# Schematic.net
KiCad netlist of a schematic drawn in Altium Designer
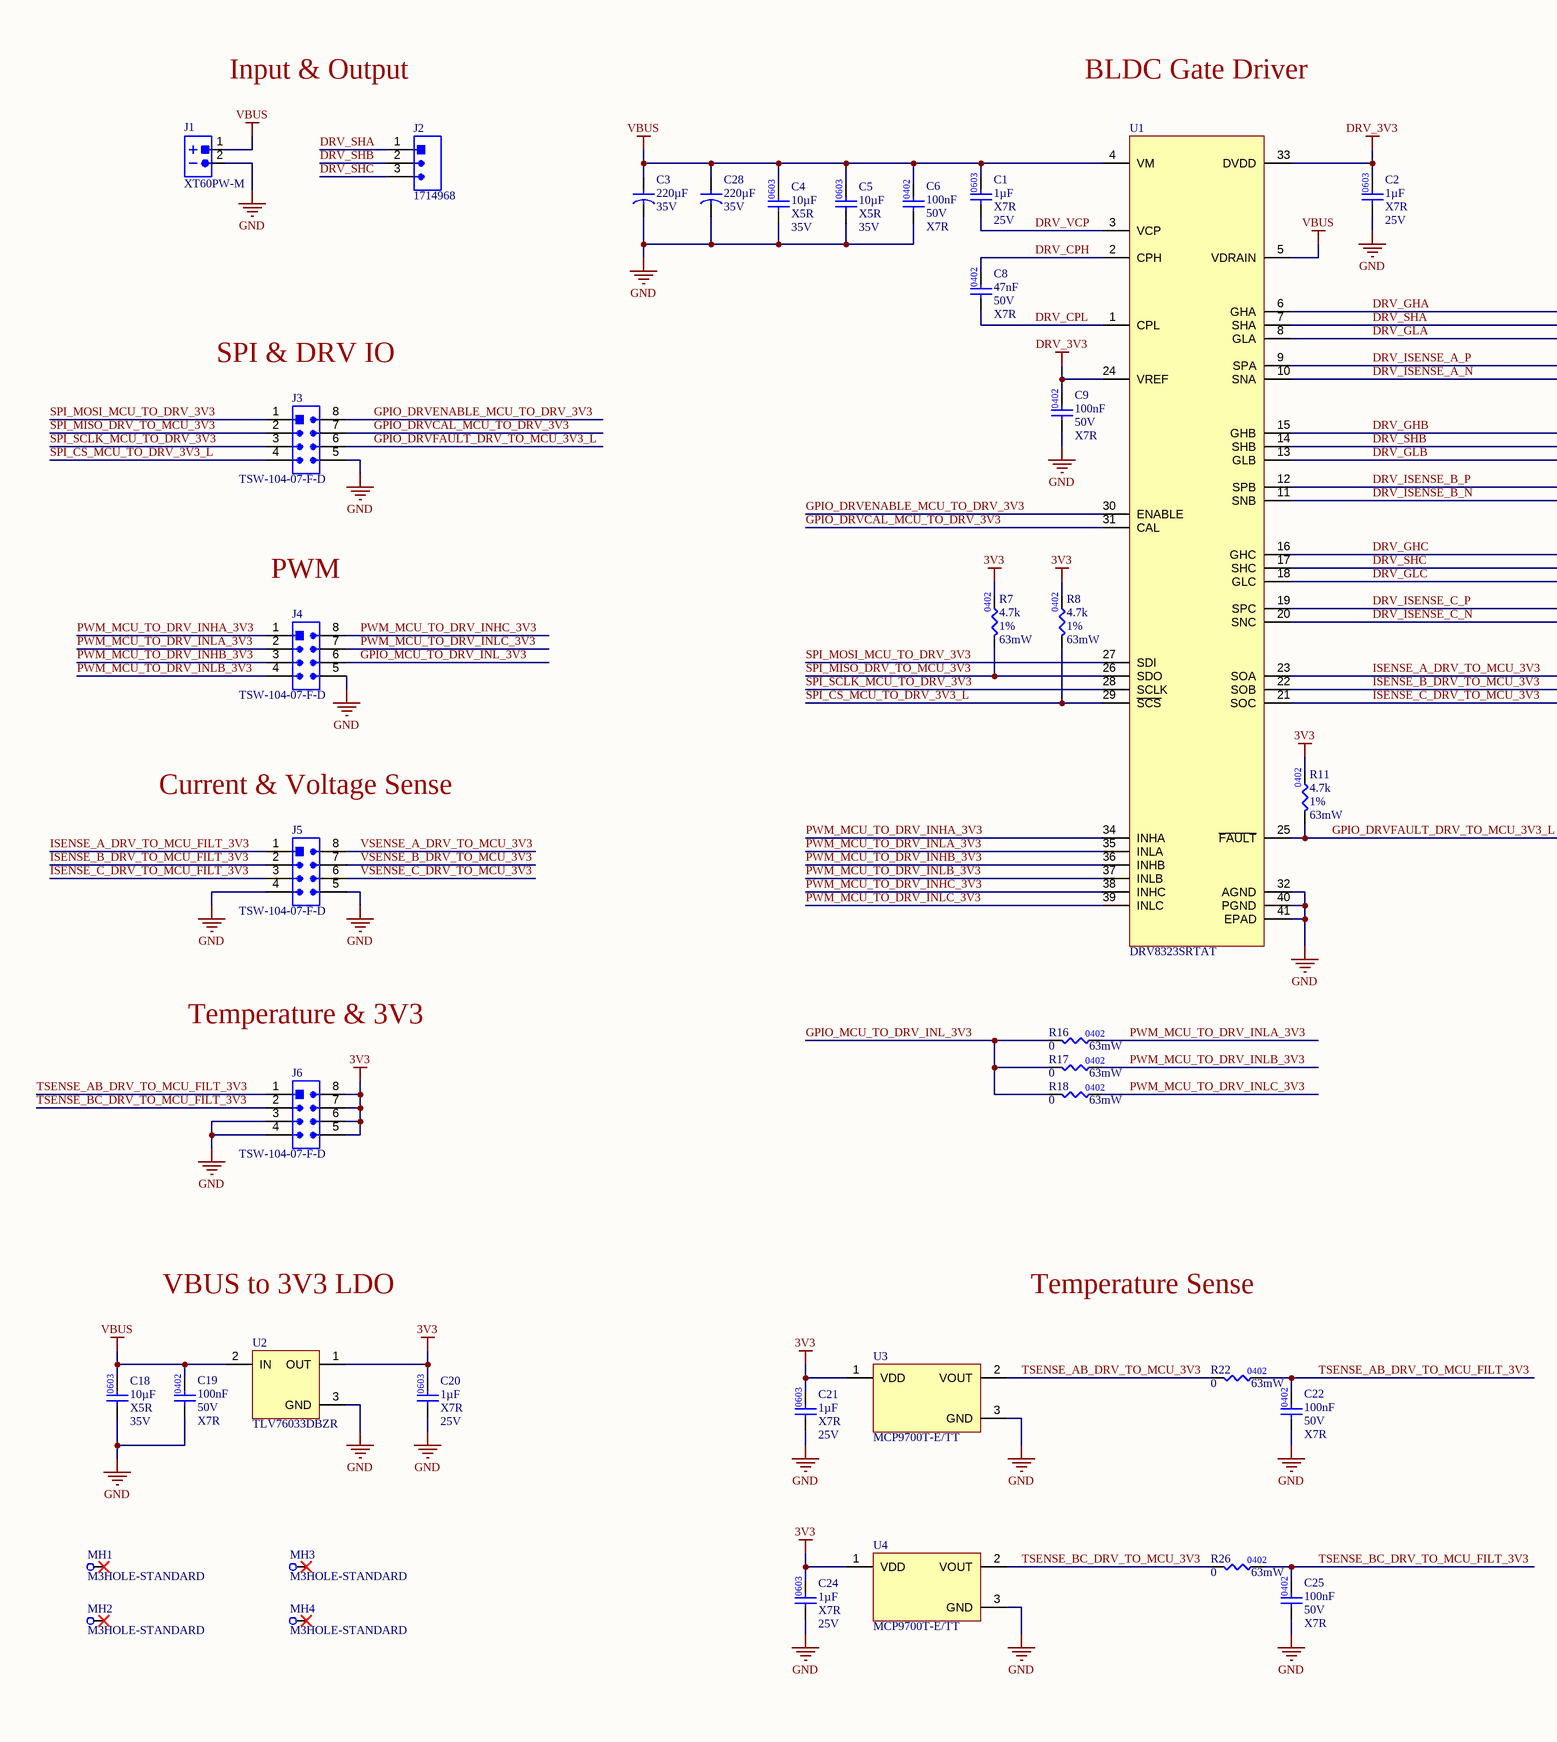
[diagram p0: Schematic.SchDoc, left]
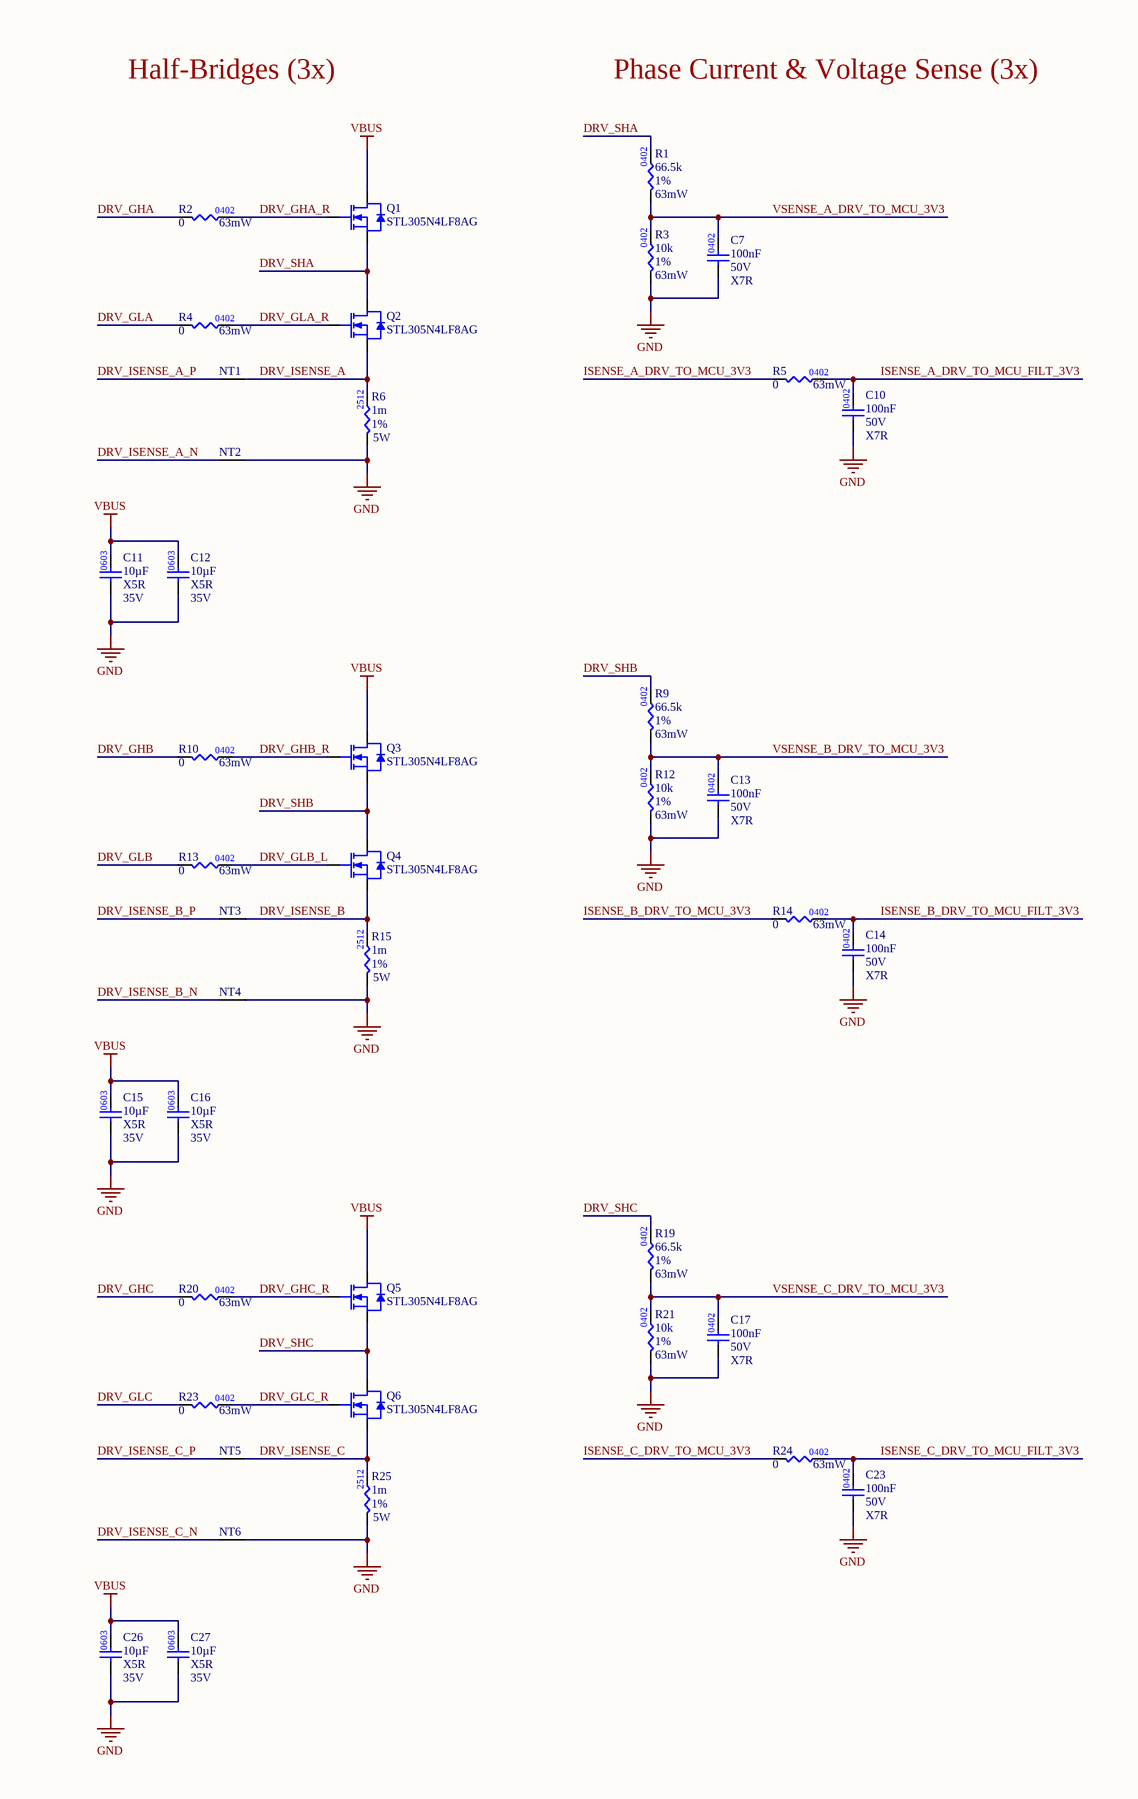
[diagram p1: Schematic.SchDoc, right]

(export (version "E")
  (design (tool "Eeschema 10.0.6"))
  (components
    (comp (ref "C1")
      (value "1µF")
      (footprint ".CAP_0603-Footprint-1")
      (description "CAP CER 1UF 25V X7R 0603")
      (fields
        (field (name "TEMPERATURE COEFFICIENT") "X7R")
        (field (name "VOLTAGE RATING") "25V")
        (field (name "TOLERANCE") "10%")
        (field (name "Comment") "CL10B105KA8NNNC")
      )
      (libsource (lib "Americas - University of Waterloo - Kevin Li Capstone 2025") (part ".CAP_0603-Symbol-1"))
    )
    (comp (ref "C2")
      (value "1µF")
      (footprint ".CAP_0603-Footprint-1")
      (description "CAP CER 1UF 25V X7R 0603")
      (fields
        (field (name "TEMPERATURE COEFFICIENT") "X7R")
        (field (name "VOLTAGE RATING") "25V")
        (field (name "TOLERANCE") "10%")
        (field (name "Comment") "CL10B105KA8NNNC")
      )
      (libsource (lib "Americas - University of Waterloo - Kevin Li Capstone 2025") (part ".CAP_0603-Symbol-1"))
    )
    (comp (ref "C3")
      (value "220µF")
      (footprint "865080553014-Footprint-1")
      (description "CAP ALUM 220UF 20% 35V SMD")
      (fields
        (field (name "TOLERANCE") "20%")
        (field (name "VOLTAGE RATING") "35V")
        (field (name "Comment") "865080553014")
      )
      (libsource (lib "Americas - University of Waterloo - Kevin Li Capstone 2025") (part "865080553014-Symbol-1"))
    )
    (comp (ref "C4")
      (value "10µF")
      (footprint ".CAP_0603-Footprint-1")
      (description "CAP CER 10UF 35V X5R 0603")
      (fields
        (field (name "TEMPERATURE COEFFICIENT") "X5R")
        (field (name "VOLTAGE RATING") "35V")
        (field (name "TOLERANCE") "20%")
        (field (name "Comment") "GRM188R6YA106MA73D")
      )
      (libsource (lib "Americas - University of Waterloo - Kevin Li Capstone 2025") (part ".CAP_0603-Symbol-1"))
    )
    (comp (ref "C5")
      (value "10µF")
      (footprint ".CAP_0603-Footprint-1")
      (description "CAP CER 10UF 35V X5R 0603")
      (fields
        (field (name "TEMPERATURE COEFFICIENT") "X5R")
        (field (name "VOLTAGE RATING") "35V")
        (field (name "TOLERANCE") "20%")
        (field (name "Comment") "GRM188R6YA106MA73D")
      )
      (libsource (lib "Americas - University of Waterloo - Kevin Li Capstone 2025") (part ".CAP_0603-Symbol-1"))
    )
    (comp (ref "C6")
      (value "100nF")
      (footprint ".CAP_0402-Footprint-1")
      (description "CAP CER 0.1UF 50V X7R 0402")
      (fields
        (field (name "VOLTAGE RATING") "50V")
        (field (name "TEMPERATURE COEFFICIENT") "X7R")
        (field (name "TOLERANCE") "10%")
        (field (name "Comment") "GCM155R71H104KE02D")
      )
      (libsource (lib "Americas - University of Waterloo - Kevin Li Capstone 2025") (part ".CAP_0402-Symbol-1"))
    )
    (comp (ref "C7")
      (value "100nF")
      (footprint ".CAP_0402-Footprint-1")
      (description "CAP CER 0.1UF 50V X7R 0402")
      (fields
        (field (name "VOLTAGE RATING") "50V")
        (field (name "TEMPERATURE COEFFICIENT") "X7R")
        (field (name "TOLERANCE") "10%")
        (field (name "Comment") "GCM155R71H104KE02D")
      )
      (libsource (lib "Americas - University of Waterloo - Kevin Li Capstone 2025") (part ".CAP_0402-Symbol-1"))
    )
    (comp (ref "C8")
      (value "47nF")
      (footprint ".CAP_0402-Footprint-1")
      (description "CAP CER 0.047UF 50V X7R 0402")
      (fields
        (field (name "VOLTAGE RATING") "50V")
        (field (name "TEMPERATURE COEFFICIENT") "X7R")
        (field (name "TOLERANCE") "10%")
        (field (name "Comment") "GRM155R71H473KE14D")
      )
      (libsource (lib "Americas - University of Waterloo - Kevin Li Capstone 2025") (part ".CAP_0402-Symbol-1"))
    )
    (comp (ref "C9")
      (value "100nF")
      (footprint ".CAP_0402-Footprint-1")
      (description "CAP CER 0.1UF 50V X7R 0402")
      (fields
        (field (name "VOLTAGE RATING") "50V")
        (field (name "TEMPERATURE COEFFICIENT") "X7R")
        (field (name "TOLERANCE") "10%")
        (field (name "Comment") "GCM155R71H104KE02D")
      )
      (libsource (lib "Americas - University of Waterloo - Kevin Li Capstone 2025") (part ".CAP_0402-Symbol-1"))
    )
    (comp (ref "C10")
      (value "100nF")
      (footprint ".CAP_0402-Footprint-1")
      (description "CAP CER 0.1UF 50V X7R 0402")
      (fields
        (field (name "VOLTAGE RATING") "50V")
        (field (name "TEMPERATURE COEFFICIENT") "X7R")
        (field (name "TOLERANCE") "10%")
        (field (name "Comment") "GCM155R71H104KE02D")
      )
      (libsource (lib "Americas - University of Waterloo - Kevin Li Capstone 2025") (part ".CAP_0402-Symbol-1"))
    )
    (comp (ref "C11")
      (value "10µF")
      (footprint ".CAP_0603-Footprint-1")
      (description "CAP CER 10UF 35V X5R 0603")
      (fields
        (field (name "TEMPERATURE COEFFICIENT") "X5R")
        (field (name "VOLTAGE RATING") "35V")
        (field (name "TOLERANCE") "20%")
        (field (name "Comment") "GRM188R6YA106MA73D")
      )
      (libsource (lib "Americas - University of Waterloo - Kevin Li Capstone 2025") (part ".CAP_0603-Symbol-1"))
    )
    (comp (ref "C12")
      (value "10µF")
      (footprint ".CAP_0603-Footprint-1")
      (description "CAP CER 10UF 35V X5R 0603")
      (fields
        (field (name "TEMPERATURE COEFFICIENT") "X5R")
        (field (name "VOLTAGE RATING") "35V")
        (field (name "TOLERANCE") "20%")
        (field (name "Comment") "GRM188R6YA106MA73D")
      )
      (libsource (lib "Americas - University of Waterloo - Kevin Li Capstone 2025") (part ".CAP_0603-Symbol-1"))
    )
    (comp (ref "C13")
      (value "100nF")
      (footprint ".CAP_0402-Footprint-1")
      (description "CAP CER 0.1UF 50V X7R 0402")
      (fields
        (field (name "VOLTAGE RATING") "50V")
        (field (name "TEMPERATURE COEFFICIENT") "X7R")
        (field (name "TOLERANCE") "10%")
        (field (name "Comment") "GCM155R71H104KE02D")
      )
      (libsource (lib "Americas - University of Waterloo - Kevin Li Capstone 2025") (part ".CAP_0402-Symbol-1"))
    )
    (comp (ref "C14")
      (value "100nF")
      (footprint ".CAP_0402-Footprint-1")
      (description "CAP CER 0.1UF 50V X7R 0402")
      (fields
        (field (name "VOLTAGE RATING") "50V")
        (field (name "TEMPERATURE COEFFICIENT") "X7R")
        (field (name "TOLERANCE") "10%")
        (field (name "Comment") "GCM155R71H104KE02D")
      )
      (libsource (lib "Americas - University of Waterloo - Kevin Li Capstone 2025") (part ".CAP_0402-Symbol-1"))
    )
    (comp (ref "C15")
      (value "10µF")
      (footprint ".CAP_0603-Footprint-1")
      (description "CAP CER 10UF 35V X5R 0603")
      (fields
        (field (name "TEMPERATURE COEFFICIENT") "X5R")
        (field (name "VOLTAGE RATING") "35V")
        (field (name "TOLERANCE") "20%")
        (field (name "Comment") "GRM188R6YA106MA73D")
      )
      (libsource (lib "Americas - University of Waterloo - Kevin Li Capstone 2025") (part ".CAP_0603-Symbol-1"))
    )
    (comp (ref "C16")
      (value "10µF")
      (footprint ".CAP_0603-Footprint-1")
      (description "CAP CER 10UF 35V X5R 0603")
      (fields
        (field (name "TEMPERATURE COEFFICIENT") "X5R")
        (field (name "VOLTAGE RATING") "35V")
        (field (name "TOLERANCE") "20%")
        (field (name "Comment") "GRM188R6YA106MA73D")
      )
      (libsource (lib "Americas - University of Waterloo - Kevin Li Capstone 2025") (part ".CAP_0603-Symbol-1"))
    )
    (comp (ref "C17")
      (value "100nF")
      (footprint ".CAP_0402-Footprint-1")
      (description "CAP CER 0.1UF 50V X7R 0402")
      (fields
        (field (name "VOLTAGE RATING") "50V")
        (field (name "TEMPERATURE COEFFICIENT") "X7R")
        (field (name "TOLERANCE") "10%")
        (field (name "Comment") "GCM155R71H104KE02D")
      )
      (libsource (lib "Americas - University of Waterloo - Kevin Li Capstone 2025") (part ".CAP_0402-Symbol-1"))
    )
    (comp (ref "C18")
      (value "10µF")
      (footprint ".CAP_0603-Footprint-1")
      (description "CAP CER 10UF 35V X5R 0603")
      (fields
        (field (name "TEMPERATURE COEFFICIENT") "X5R")
        (field (name "VOLTAGE RATING") "35V")
        (field (name "TOLERANCE") "20%")
        (field (name "Comment") "GRM188R6YA106MA73D")
      )
      (libsource (lib "Americas - University of Waterloo - Kevin Li Capstone 2025") (part ".CAP_0603-Symbol-1"))
    )
    (comp (ref "C19")
      (value "100nF")
      (footprint ".CAP_0402-Footprint-1")
      (description "CAP CER 0.1UF 50V X7R 0402")
      (fields
        (field (name "VOLTAGE RATING") "50V")
        (field (name "TEMPERATURE COEFFICIENT") "X7R")
        (field (name "TOLERANCE") "10%")
        (field (name "Comment") "GCM155R71H104KE02D")
      )
      (libsource (lib "Americas - University of Waterloo - Kevin Li Capstone 2025") (part ".CAP_0402-Symbol-1"))
    )
    (comp (ref "C20")
      (value "1µF")
      (footprint ".CAP_0603-Footprint-1")
      (description "CAP CER 1UF 25V X7R 0603")
      (fields
        (field (name "TEMPERATURE COEFFICIENT") "X7R")
        (field (name "VOLTAGE RATING") "25V")
        (field (name "TOLERANCE") "10%")
        (field (name "Comment") "CL10B105KA8NNNC")
      )
      (libsource (lib "Americas - University of Waterloo - Kevin Li Capstone 2025") (part ".CAP_0603-Symbol-1"))
    )
    (comp (ref "C21")
      (value "1µF")
      (footprint ".CAP_0603-Footprint-1")
      (description "CAP CER 1UF 25V X7R 0603")
      (fields
        (field (name "TEMPERATURE COEFFICIENT") "X7R")
        (field (name "VOLTAGE RATING") "25V")
        (field (name "TOLERANCE") "10%")
        (field (name "Comment") "CL10B105KA8NNNC")
      )
      (libsource (lib "Americas - University of Waterloo - Kevin Li Capstone 2025") (part ".CAP_0603-Symbol-1"))
    )
    (comp (ref "C22")
      (value "100nF")
      (footprint ".CAP_0402-Footprint-1")
      (description "CAP CER 0.1UF 50V X7R 0402")
      (fields
        (field (name "VOLTAGE RATING") "50V")
        (field (name "TEMPERATURE COEFFICIENT") "X7R")
        (field (name "TOLERANCE") "10%")
        (field (name "Comment") "GCM155R71H104KE02D")
      )
      (libsource (lib "Americas - University of Waterloo - Kevin Li Capstone 2025") (part ".CAP_0402-Symbol-1"))
    )
    (comp (ref "C23")
      (value "100nF")
      (footprint ".CAP_0402-Footprint-1")
      (description "CAP CER 0.1UF 50V X7R 0402")
      (fields
        (field (name "VOLTAGE RATING") "50V")
        (field (name "TEMPERATURE COEFFICIENT") "X7R")
        (field (name "TOLERANCE") "10%")
        (field (name "Comment") "GCM155R71H104KE02D")
      )
      (libsource (lib "Americas - University of Waterloo - Kevin Li Capstone 2025") (part ".CAP_0402-Symbol-1"))
    )
    (comp (ref "C24")
      (value "1µF")
      (footprint ".CAP_0603-Footprint-1")
      (description "CAP CER 1UF 25V X7R 0603")
      (fields
        (field (name "TEMPERATURE COEFFICIENT") "X7R")
        (field (name "VOLTAGE RATING") "25V")
        (field (name "TOLERANCE") "10%")
        (field (name "Comment") "CL10B105KA8NNNC")
      )
      (libsource (lib "Americas - University of Waterloo - Kevin Li Capstone 2025") (part ".CAP_0603-Symbol-1"))
    )
    (comp (ref "C25")
      (value "100nF")
      (footprint ".CAP_0402-Footprint-1")
      (description "CAP CER 0.1UF 50V X7R 0402")
      (fields
        (field (name "VOLTAGE RATING") "50V")
        (field (name "TEMPERATURE COEFFICIENT") "X7R")
        (field (name "TOLERANCE") "10%")
        (field (name "Comment") "GCM155R71H104KE02D")
      )
      (libsource (lib "Americas - University of Waterloo - Kevin Li Capstone 2025") (part ".CAP_0402-Symbol-1"))
    )
    (comp (ref "C26")
      (value "10µF")
      (footprint ".CAP_0603-Footprint-1")
      (description "CAP CER 10UF 35V X5R 0603")
      (fields
        (field (name "TEMPERATURE COEFFICIENT") "X5R")
        (field (name "VOLTAGE RATING") "35V")
        (field (name "TOLERANCE") "20%")
        (field (name "Comment") "GRM188R6YA106MA73D")
      )
      (libsource (lib "Americas - University of Waterloo - Kevin Li Capstone 2025") (part ".CAP_0603-Symbol-1"))
    )
    (comp (ref "C27")
      (value "10µF")
      (footprint ".CAP_0603-Footprint-1")
      (description "CAP CER 10UF 35V X5R 0603")
      (fields
        (field (name "TEMPERATURE COEFFICIENT") "X5R")
        (field (name "VOLTAGE RATING") "35V")
        (field (name "TOLERANCE") "20%")
        (field (name "Comment") "GRM188R6YA106MA73D")
      )
      (libsource (lib "Americas - University of Waterloo - Kevin Li Capstone 2025") (part ".CAP_0603-Symbol-1"))
    )
    (comp (ref "C28")
      (value "220µF")
      (footprint "865080553014-Footprint-1")
      (description "CAP ALUM 220UF 20% 35V SMD")
      (fields
        (field (name "TOLERANCE") "20%")
        (field (name "VOLTAGE RATING") "35V")
        (field (name "Comment") "865080553014")
      )
      (libsource (lib "Americas - University of Waterloo - Kevin Li Capstone 2025") (part "865080553014-Symbol-1"))
    )
    (comp (ref "J1")
      (value "XT60PW-M")
      (footprint "XT60PW-M-Footprint-1")
      (description "XT60PW-M Connector")
      (libsource (lib "Americas - University of Waterloo - Kevin Li Capstone 2025") (part "XT60PW-M-Symbol-1"))
    )
    (comp (ref "J2")
      (value "1714968")
      (footprint "1714968-Footprint-1")
      (description "TERM BLK 3P SIDE ENT 6.35MM PCB")
      (libsource (lib "Americas - University of Waterloo - Kevin Li Capstone 2025") (part "1714968-Symbol-1"))
    )
    (comp (ref "J3")
      (value "TSW-104-07-F-D")
      (footprint "TSW-104-07-F-D-Footprint-1")
      (description "CONN HEADER VERT 8POS 2.54MM")
      (libsource (lib "Americas - University of Waterloo - Kevin Li Capstone 2025") (part "TSW-104-07-F-D-Symbol-1"))
    )
    (comp (ref "J4")
      (value "TSW-104-07-F-D")
      (footprint "TSW-104-07-F-D-Footprint-1")
      (description "CONN HEADER VERT 8POS 2.54MM")
      (libsource (lib "Americas - University of Waterloo - Kevin Li Capstone 2025") (part "TSW-104-07-F-D-Symbol-1"))
    )
    (comp (ref "J5")
      (value "TSW-104-07-F-D")
      (footprint "TSW-104-07-F-D-Footprint-1")
      (description "CONN HEADER VERT 8POS 2.54MM")
      (libsource (lib "Americas - University of Waterloo - Kevin Li Capstone 2025") (part "TSW-104-07-F-D-Symbol-1"))
    )
    (comp (ref "J6")
      (value "TSW-104-07-F-D")
      (footprint "TSW-104-07-F-D-Footprint-1")
      (description "CONN HEADER VERT 8POS 2.54MM")
      (libsource (lib "Americas - University of Waterloo - Kevin Li Capstone 2025") (part "TSW-104-07-F-D-Symbol-1"))
    )
    (comp (ref "MH1")
      (value "M3HOLE-STANDARD")
      (footprint "M3HOLE-STANDARD-Footprint-1")
      (description "M3 Mounting Hole")
      (libsource (lib "Americas - University of Waterloo - Kevin Li Capstone 2025") (part "M3HOLE-STANDARD-Symbol-1"))
    )
    (comp (ref "MH2")
      (value "M3HOLE-STANDARD")
      (footprint "M3HOLE-STANDARD-Footprint-1")
      (description "M3 Mounting Hole")
      (libsource (lib "Americas - University of Waterloo - Kevin Li Capstone 2025") (part "M3HOLE-STANDARD-Symbol-1"))
    )
    (comp (ref "MH3")
      (value "M3HOLE-STANDARD")
      (footprint "M3HOLE-STANDARD-Footprint-1")
      (description "M3 Mounting Hole")
      (libsource (lib "Americas - University of Waterloo - Kevin Li Capstone 2025") (part "M3HOLE-STANDARD-Symbol-1"))
    )
    (comp (ref "MH4")
      (value "M3HOLE-STANDARD")
      (footprint "M3HOLE-STANDARD-Footprint-1")
      (description "M3 Mounting Hole")
      (libsource (lib "Americas - University of Waterloo - Kevin Li Capstone 2025") (part "M3HOLE-STANDARD-Symbol-1"))
    )
    (comp (ref "NT1")
      (value "NET_TIE_127um")
      (footprint "NET_TIE_127um-Footprint-1")
      (description "127um NET TIE")
      (libsource (lib "Americas - University of Waterloo - Kevin Li Capstone 2025") (part "NET_TIE_127um-Symbol-1"))
    )
    (comp (ref "NT2")
      (value "NET_TIE_127um")
      (footprint "NET_TIE_127um-Footprint-1")
      (description "127um NET TIE")
      (libsource (lib "Americas - University of Waterloo - Kevin Li Capstone 2025") (part "NET_TIE_127um-Symbol-1"))
    )
    (comp (ref "NT3")
      (value "NET_TIE_127um")
      (footprint "NET_TIE_127um-Footprint-1")
      (description "127um NET TIE")
      (libsource (lib "Americas - University of Waterloo - Kevin Li Capstone 2025") (part "NET_TIE_127um-Symbol-1"))
    )
    (comp (ref "NT4")
      (value "NET_TIE_127um")
      (footprint "NET_TIE_127um-Footprint-1")
      (description "127um NET TIE")
      (libsource (lib "Americas - University of Waterloo - Kevin Li Capstone 2025") (part "NET_TIE_127um-Symbol-1"))
    )
    (comp (ref "NT5")
      (value "NET_TIE_127um")
      (footprint "NET_TIE_127um-Footprint-1")
      (description "127um NET TIE")
      (libsource (lib "Americas - University of Waterloo - Kevin Li Capstone 2025") (part "NET_TIE_127um-Symbol-1"))
    )
    (comp (ref "NT6")
      (value "NET_TIE_127um")
      (footprint "NET_TIE_127um-Footprint-1")
      (description "127um NET TIE")
      (libsource (lib "Americas - University of Waterloo - Kevin Li Capstone 2025") (part "NET_TIE_127um-Symbol-1"))
    )
    (comp (ref "Q1")
      (value "STL305N4LF8AG")
      (footprint "STL305N4LF8AG-Footprint-1")
      (description "MOSFET N-CH 40V 120A POWERFLAT 5X6 WF")
      (libsource (lib "Americas - University of Waterloo - Kevin Li Capstone 2025") (part "STL305N4LF8AG-Symbol-1"))
    )
    (comp (ref "Q2")
      (value "STL305N4LF8AG")
      (footprint "STL305N4LF8AG-Footprint-1")
      (description "MOSFET N-CH 40V 120A POWERFLAT 5X6 WF")
      (libsource (lib "Americas - University of Waterloo - Kevin Li Capstone 2025") (part "STL305N4LF8AG-Symbol-1"))
    )
    (comp (ref "Q3")
      (value "STL305N4LF8AG")
      (footprint "STL305N4LF8AG-Footprint-1")
      (description "MOSFET N-CH 40V 120A POWERFLAT 5X6 WF")
      (libsource (lib "Americas - University of Waterloo - Kevin Li Capstone 2025") (part "STL305N4LF8AG-Symbol-1"))
    )
    (comp (ref "Q4")
      (value "STL305N4LF8AG")
      (footprint "STL305N4LF8AG-Footprint-1")
      (description "MOSFET N-CH 40V 120A POWERFLAT 5X6 WF")
      (libsource (lib "Americas - University of Waterloo - Kevin Li Capstone 2025") (part "STL305N4LF8AG-Symbol-1"))
    )
    (comp (ref "Q5")
      (value "STL305N4LF8AG")
      (footprint "STL305N4LF8AG-Footprint-1")
      (description "MOSFET N-CH 40V 120A POWERFLAT 5X6 WF")
      (libsource (lib "Americas - University of Waterloo - Kevin Li Capstone 2025") (part "STL305N4LF8AG-Symbol-1"))
    )
    (comp (ref "Q6")
      (value "STL305N4LF8AG")
      (footprint "STL305N4LF8AG-Footprint-1")
      (description "MOSFET N-CH 40V 120A POWERFLAT 5X6 WF")
      (libsource (lib "Americas - University of Waterloo - Kevin Li Capstone 2025") (part "STL305N4LF8AG-Symbol-1"))
    )
    (comp (ref "R1")
      (value "66.5k")
      (footprint ".RES_0402-Footprint-1")
      (description "RES 66.5K OHM 1% 1/16W 0402")
      (fields
        (field (name "TOLERANCE") "1%")
        (field (name "POWER") "63mW")
        (field (name "Comment") "RC0402FR-0766K5L")
      )
      (libsource (lib "Americas - University of Waterloo - Kevin Li Capstone 2025") (part ".RES_0402-Symbol-1"))
    )
    (comp (ref "R2")
      (value "0")
      (footprint ".RES_0402-Footprint-1")
      (description "RES 0 OHM JUMPER 1/16W 0402")
      (fields (field (name "POWER") "63mW") (field (name "Comment") "RC0402JR-070RL"))
      (libsource (lib "Americas - University of Waterloo - Kevin Li Capstone 2025") (part ".RES_0402-Symbol-1"))
    )
    (comp (ref "R3")
      (value "10k")
      (footprint ".RES_0402-Footprint-1")
      (description "RES 10K OHM 1% 1/16W 0402")
      (fields
        (field (name "TOLERANCE") "1%")
        (field (name "POWER") "63mW")
        (field (name "Comment") "RC0402FR-0710KL")
      )
      (libsource (lib "Americas - University of Waterloo - Kevin Li Capstone 2025") (part ".RES_0402-Symbol-1"))
    )
    (comp (ref "R4")
      (value "0")
      (footprint ".RES_0402-Footprint-1")
      (description "RES 0 OHM JUMPER 1/16W 0402")
      (fields (field (name "POWER") "63mW") (field (name "Comment") "RC0402JR-070RL"))
      (libsource (lib "Americas - University of Waterloo - Kevin Li Capstone 2025") (part ".RES_0402-Symbol-1"))
    )
    (comp (ref "R5")
      (value "0")
      (footprint ".RES_0402-Footprint-1")
      (description "RES 0 OHM JUMPER 1/16W 0402")
      (fields (field (name "POWER") "63mW") (field (name "Comment") "RC0402JR-070RL"))
      (libsource (lib "Americas - University of Waterloo - Kevin Li Capstone 2025") (part ".RES_0402-Symbol-1"))
    )
    (comp (ref "R6")
      (value "1m")
      (footprint "WSLF25121L000FEA-Footprint-1")
      (description "RES 0.001 OHM 1% 5W 2512")
      (fields
        (field (name "POWER") "5W")
        (field (name "TOLERANCE") "1%")
        (field (name "Comment") "WSLF25121L000FEA")
      )
      (libsource (lib "Americas - University of Waterloo - Kevin Li Capstone 2025") (part "WSLF25121L000FEA-Symbol-1"))
    )
    (comp (ref "R7")
      (value "4.7k")
      (footprint ".RES_0402-Footprint-1")
      (description "RES 4.7K OHM 1% 1/16W 0402")
      (fields
        (field (name "TOLERANCE") "1%")
        (field (name "POWER") "63mW")
        (field (name "Comment") "RC0402FR-074K7L")
      )
      (libsource (lib "Americas - University of Waterloo - Kevin Li Capstone 2025") (part ".RES_0402-Symbol-1"))
    )
    (comp (ref "R8")
      (value "4.7k")
      (footprint ".RES_0402-Footprint-1")
      (description "RES 4.7K OHM 1% 1/16W 0402")
      (fields
        (field (name "TOLERANCE") "1%")
        (field (name "POWER") "63mW")
        (field (name "Comment") "RC0402FR-074K7L")
      )
      (libsource (lib "Americas - University of Waterloo - Kevin Li Capstone 2025") (part ".RES_0402-Symbol-1"))
    )
    (comp (ref "R9")
      (value "66.5k")
      (footprint ".RES_0402-Footprint-1")
      (description "RES 66.5K OHM 1% 1/16W 0402")
      (fields
        (field (name "TOLERANCE") "1%")
        (field (name "POWER") "63mW")
        (field (name "Comment") "RC0402FR-0766K5L")
      )
      (libsource (lib "Americas - University of Waterloo - Kevin Li Capstone 2025") (part ".RES_0402-Symbol-1"))
    )
    (comp (ref "R10")
      (value "0")
      (footprint ".RES_0402-Footprint-1")
      (description "RES 0 OHM JUMPER 1/16W 0402")
      (fields (field (name "POWER") "63mW") (field (name "Comment") "RC0402JR-070RL"))
      (libsource (lib "Americas - University of Waterloo - Kevin Li Capstone 2025") (part ".RES_0402-Symbol-1"))
    )
    (comp (ref "R11")
      (value "4.7k")
      (footprint ".RES_0402-Footprint-1")
      (description "RES 4.7K OHM 1% 1/16W 0402")
      (fields
        (field (name "TOLERANCE") "1%")
        (field (name "POWER") "63mW")
        (field (name "Comment") "RC0402FR-074K7L")
      )
      (libsource (lib "Americas - University of Waterloo - Kevin Li Capstone 2025") (part ".RES_0402-Symbol-1"))
    )
    (comp (ref "R12")
      (value "10k")
      (footprint ".RES_0402-Footprint-1")
      (description "RES 10K OHM 1% 1/16W 0402")
      (fields
        (field (name "TOLERANCE") "1%")
        (field (name "POWER") "63mW")
        (field (name "Comment") "RC0402FR-0710KL")
      )
      (libsource (lib "Americas - University of Waterloo - Kevin Li Capstone 2025") (part ".RES_0402-Symbol-1"))
    )
    (comp (ref "R13")
      (value "0")
      (footprint ".RES_0402-Footprint-1")
      (description "RES 0 OHM JUMPER 1/16W 0402")
      (fields (field (name "POWER") "63mW") (field (name "Comment") "RC0402JR-070RL"))
      (libsource (lib "Americas - University of Waterloo - Kevin Li Capstone 2025") (part ".RES_0402-Symbol-1"))
    )
    (comp (ref "R14")
      (value "0")
      (footprint ".RES_0402-Footprint-1")
      (description "RES 0 OHM JUMPER 1/16W 0402")
      (fields (field (name "POWER") "63mW") (field (name "Comment") "RC0402JR-070RL"))
      (libsource (lib "Americas - University of Waterloo - Kevin Li Capstone 2025") (part ".RES_0402-Symbol-1"))
    )
    (comp (ref "R15")
      (value "1m")
      (footprint "WSLF25121L000FEA-Footprint-1")
      (description "RES 0.001 OHM 1% 5W 2512")
      (fields
        (field (name "POWER") "5W")
        (field (name "TOLERANCE") "1%")
        (field (name "Comment") "WSLF25121L000FEA")
      )
      (libsource (lib "Americas - University of Waterloo - Kevin Li Capstone 2025") (part "WSLF25121L000FEA-Symbol-1"))
    )
    (comp (ref "R16")
      (value "0")
      (footprint ".RES_0402-Footprint-1")
      (description "RES 0 OHM JUMPER 1/16W 0402")
      (fields (field (name "POWER") "63mW") (field (name "Comment") "RC0402JR-070RL"))
      (libsource (lib "Americas - University of Waterloo - Kevin Li Capstone 2025") (part ".RES_0402-Symbol-1"))
    )
    (comp (ref "R17")
      (value "0")
      (footprint ".RES_0402-Footprint-1")
      (description "RES 0 OHM JUMPER 1/16W 0402")
      (fields (field (name "POWER") "63mW") (field (name "Comment") "RC0402JR-070RL"))
      (libsource (lib "Americas - University of Waterloo - Kevin Li Capstone 2025") (part ".RES_0402-Symbol-1"))
    )
    (comp (ref "R18")
      (value "0")
      (footprint ".RES_0402-Footprint-1")
      (description "RES 0 OHM JUMPER 1/16W 0402")
      (fields (field (name "POWER") "63mW") (field (name "Comment") "RC0402JR-070RL"))
      (libsource (lib "Americas - University of Waterloo - Kevin Li Capstone 2025") (part ".RES_0402-Symbol-1"))
    )
    (comp (ref "R19")
      (value "66.5k")
      (footprint ".RES_0402-Footprint-1")
      (description "RES 66.5K OHM 1% 1/16W 0402")
      (fields
        (field (name "TOLERANCE") "1%")
        (field (name "POWER") "63mW")
        (field (name "Comment") "RC0402FR-0766K5L")
      )
      (libsource (lib "Americas - University of Waterloo - Kevin Li Capstone 2025") (part ".RES_0402-Symbol-1"))
    )
    (comp (ref "R20")
      (value "0")
      (footprint ".RES_0402-Footprint-1")
      (description "RES 0 OHM JUMPER 1/16W 0402")
      (fields (field (name "POWER") "63mW") (field (name "Comment") "RC0402JR-070RL"))
      (libsource (lib "Americas - University of Waterloo - Kevin Li Capstone 2025") (part ".RES_0402-Symbol-1"))
    )
    (comp (ref "R21")
      (value "10k")
      (footprint ".RES_0402-Footprint-1")
      (description "RES 10K OHM 1% 1/16W 0402")
      (fields
        (field (name "TOLERANCE") "1%")
        (field (name "POWER") "63mW")
        (field (name "Comment") "RC0402FR-0710KL")
      )
      (libsource (lib "Americas - University of Waterloo - Kevin Li Capstone 2025") (part ".RES_0402-Symbol-1"))
    )
    (comp (ref "R22")
      (value "0")
      (footprint ".RES_0402-Footprint-1")
      (description "RES 0 OHM JUMPER 1/16W 0402")
      (fields (field (name "POWER") "63mW") (field (name "Comment") "RC0402JR-070RL"))
      (libsource (lib "Americas - University of Waterloo - Kevin Li Capstone 2025") (part ".RES_0402-Symbol-1"))
    )
    (comp (ref "R23")
      (value "0")
      (footprint ".RES_0402-Footprint-1")
      (description "RES 0 OHM JUMPER 1/16W 0402")
      (fields (field (name "POWER") "63mW") (field (name "Comment") "RC0402JR-070RL"))
      (libsource (lib "Americas - University of Waterloo - Kevin Li Capstone 2025") (part ".RES_0402-Symbol-1"))
    )
    (comp (ref "R24")
      (value "0")
      (footprint ".RES_0402-Footprint-1")
      (description "RES 0 OHM JUMPER 1/16W 0402")
      (fields (field (name "POWER") "63mW") (field (name "Comment") "RC0402JR-070RL"))
      (libsource (lib "Americas - University of Waterloo - Kevin Li Capstone 2025") (part ".RES_0402-Symbol-1"))
    )
    (comp (ref "R25")
      (value "1m")
      (footprint "WSLF25121L000FEA-Footprint-1")
      (description "RES 0.001 OHM 1% 5W 2512")
      (fields
        (field (name "POWER") "5W")
        (field (name "TOLERANCE") "1%")
        (field (name "Comment") "WSLF25121L000FEA")
      )
      (libsource (lib "Americas - University of Waterloo - Kevin Li Capstone 2025") (part "WSLF25121L000FEA-Symbol-1"))
    )
    (comp (ref "R26")
      (value "0")
      (footprint ".RES_0402-Footprint-1")
      (description "RES 0 OHM JUMPER 1/16W 0402")
      (fields (field (name "POWER") "63mW") (field (name "Comment") "RC0402JR-070RL"))
      (libsource (lib "Americas - University of Waterloo - Kevin Li Capstone 2025") (part ".RES_0402-Symbol-1"))
    )
    (comp (ref "U1")
      (value "DRV8323SRTAT")
      (footprint "QFN50P600X600X80_HS-41N")
      (description "IC MTR DRV MULTPHAS 6-60V 40WQFN")
      (libsource (lib "Americas - University of Waterloo - Kevin Li Capstone 2025") (part "DRV8323SRTAT-Symbol-1"))
    )
    (comp (ref "U2")
      (value "TLV76033DBZR")
      (footprint "TLV76033DBZR-Footprint-1")
      (description "IC REG LINEAR 3.3V 100MA SOT23-3")
      (libsource (lib "Americas - University of Waterloo - Kevin Li Capstone 2025") (part "TLV76033DBZR-Symbol-1"))
    )
    (comp (ref "U3")
      (value "MCP9700T-E/TT")
      (footprint "MCP9700T-E_TT-Footprint-1")
      (description "SENSOR ANALOG -40C-125C SOT23-3")
      (libsource (lib "Americas - University of Waterloo - Kevin Li Capstone 2025") (part "MCP9700T-E_TT-Symbol-1"))
    )
    (comp (ref "U4")
      (value "MCP9700T-E/TT")
      (footprint "MCP9700T-E_TT-Footprint-1")
      (description "SENSOR ANALOG -40C-125C SOT23-3")
      (libsource (lib "Americas - University of Waterloo - Kevin Li Capstone 2025") (part "MCP9700T-E_TT-Symbol-1"))
    )
  )
  (nets
    (net (code "1") (name "/DRV_CPH") (class "Default")
      (node (ref "C8") (pin "2") (pinfunction "2_2") (pintype "passive"))
      (node (ref "U1") (pin "2") (pinfunction "CPH_2") (pintype "passive"))
    )
    (net (code "2") (name "/DRV_CPL") (class "Default")
      (node (ref "C8") (pin "1") (pinfunction "1_1") (pintype "passive"))
      (node (ref "U1") (pin "1") (pinfunction "CPL_1") (pintype "passive"))
    )
    (net (code "3") (name "/DRV_GHA") (class "Default")
      (node (ref "R2") (pin "1") (pinfunction "1_1") (pintype "passive"))
      (node (ref "U1") (pin "6") (pinfunction "GHA_6") (pintype "passive"))
    )
    (net (code "4") (name "/DRV_GHA_R") (class "Default")
      (node (ref "Q1") (pin "1") (pinfunction "G_1") (pintype "passive"))
      (node (ref "R2") (pin "2") (pinfunction "2_2") (pintype "passive"))
    )
    (net (code "5") (name "/DRV_GHB") (class "Default")
      (node (ref "R10") (pin "1") (pinfunction "1_1") (pintype "passive"))
      (node (ref "U1") (pin "15") (pinfunction "GHB_15") (pintype "passive"))
    )
    (net (code "6") (name "/DRV_GHB_R") (class "Default")
      (node (ref "Q3") (pin "1") (pinfunction "G_1") (pintype "passive"))
      (node (ref "R10") (pin "2") (pinfunction "2_2") (pintype "passive"))
    )
    (net (code "7") (name "/DRV_GHC") (class "Default")
      (node (ref "R20") (pin "1") (pinfunction "1_1") (pintype "passive"))
      (node (ref "U1") (pin "16") (pinfunction "GHC_16") (pintype "passive"))
    )
    (net (code "8") (name "/DRV_GHC_R") (class "Default")
      (node (ref "Q5") (pin "1") (pinfunction "G_1") (pintype "passive"))
      (node (ref "R20") (pin "2") (pinfunction "2_2") (pintype "passive"))
    )
    (net (code "9") (name "/DRV_GLA") (class "Default")
      (node (ref "R4") (pin "1") (pinfunction "1_1") (pintype "passive"))
      (node (ref "U1") (pin "8") (pinfunction "GLA_8") (pintype "passive"))
    )
    (net (code "10") (name "/DRV_GLA_R") (class "Default")
      (node (ref "Q2") (pin "1") (pinfunction "G_1") (pintype "passive"))
      (node (ref "R4") (pin "2") (pinfunction "2_2") (pintype "passive"))
    )
    (net (code "11") (name "/DRV_GLB") (class "Default")
      (node (ref "R13") (pin "1") (pinfunction "1_1") (pintype "passive"))
      (node (ref "U1") (pin "13") (pinfunction "GLB_13") (pintype "passive"))
    )
    (net (code "12") (name "/DRV_GLB_L") (class "Default")
      (node (ref "Q4") (pin "1") (pinfunction "G_1") (pintype "passive"))
      (node (ref "R13") (pin "2") (pinfunction "2_2") (pintype "passive"))
    )
    (net (code "13") (name "/DRV_GLC") (class "Default")
      (node (ref "R23") (pin "1") (pinfunction "1_1") (pintype "passive"))
      (node (ref "U1") (pin "18") (pinfunction "GLC_18") (pintype "passive"))
    )
    (net (code "14") (name "/DRV_GLC_R") (class "Default")
      (node (ref "Q6") (pin "1") (pinfunction "G_1") (pintype "passive"))
      (node (ref "R23") (pin "2") (pinfunction "2_2") (pintype "passive"))
    )
    (net (code "15") (name "/DRV_ISENSE_A") (class "Default")
      (node (ref "NT1") (pin "2") (pinfunction "2_2") (pintype "passive"))
      (node (ref "Q2") (pin "2") (pinfunction "S_2") (pintype "passive"))
      (node (ref "R6") (pin "2") (pinfunction "2_2") (pintype "passive"))
    )
    (net (code "16") (name "/DRV_ISENSE_A_N") (class "Default")
      (node (ref "NT2") (pin "1") (pinfunction "1_1") (pintype "passive"))
      (node (ref "U1") (pin "10") (pinfunction "SNA_10") (pintype "passive"))
    )
    (net (code "17") (name "/DRV_ISENSE_A_P") (class "Default")
      (node (ref "NT1") (pin "1") (pinfunction "1_1") (pintype "passive"))
      (node (ref "U1") (pin "9") (pinfunction "SPA_9") (pintype "passive"))
    )
    (net (code "18") (name "/DRV_ISENSE_B") (class "Default")
      (node (ref "NT3") (pin "2") (pinfunction "2_2") (pintype "passive"))
      (node (ref "Q4") (pin "2") (pinfunction "S_2") (pintype "passive"))
      (node (ref "R15") (pin "2") (pinfunction "2_2") (pintype "passive"))
    )
    (net (code "19") (name "/DRV_ISENSE_B_N") (class "Default")
      (node (ref "NT4") (pin "1") (pinfunction "1_1") (pintype "passive"))
      (node (ref "U1") (pin "11") (pinfunction "SNB_11") (pintype "passive"))
    )
    (net (code "20") (name "/DRV_ISENSE_B_P") (class "Default")
      (node (ref "NT3") (pin "1") (pinfunction "1_1") (pintype "passive"))
      (node (ref "U1") (pin "12") (pinfunction "SPB_12") (pintype "passive"))
    )
    (net (code "21") (name "/DRV_ISENSE_C") (class "Default")
      (node (ref "NT5") (pin "2") (pinfunction "2_2") (pintype "passive"))
      (node (ref "Q6") (pin "2") (pinfunction "S_2") (pintype "passive"))
      (node (ref "R25") (pin "2") (pinfunction "2_2") (pintype "passive"))
    )
    (net (code "22") (name "/DRV_ISENSE_C_N") (class "Default")
      (node (ref "NT6") (pin "1") (pinfunction "1_1") (pintype "passive"))
      (node (ref "U1") (pin "20") (pinfunction "SNC_20") (pintype "passive"))
    )
    (net (code "23") (name "/DRV_ISENSE_C_P") (class "Default")
      (node (ref "NT5") (pin "1") (pinfunction "1_1") (pintype "passive"))
      (node (ref "U1") (pin "19") (pinfunction "SPC_19") (pintype "passive"))
    )
    (net (code "24") (name "/DRV_SHA") (class "Default")
      (node (ref "J2") (pin "1") (pinfunction "1_1") (pintype "passive"))
      (node (ref "Q1") (pin "2") (pinfunction "S_2") (pintype "passive"))
      (node (ref "Q2") (pin "3") (pinfunction "D_3") (pintype "passive"))
      (node (ref "R1") (pin "2") (pinfunction "2_2") (pintype "passive"))
      (node (ref "U1") (pin "7") (pinfunction "SHA_7") (pintype "passive"))
    )
    (net (code "25") (name "/DRV_SHB") (class "Default")
      (node (ref "J2") (pin "2") (pinfunction "2_2") (pintype "passive"))
      (node (ref "Q3") (pin "2") (pinfunction "S_2") (pintype "passive"))
      (node (ref "Q4") (pin "3") (pinfunction "D_3") (pintype "passive"))
      (node (ref "R9") (pin "2") (pinfunction "2_2") (pintype "passive"))
      (node (ref "U1") (pin "14") (pinfunction "SHB_14") (pintype "passive"))
    )
    (net (code "26") (name "/DRV_SHC") (class "Default")
      (node (ref "J2") (pin "3") (pinfunction "3_3") (pintype "passive"))
      (node (ref "Q5") (pin "2") (pinfunction "S_2") (pintype "passive"))
      (node (ref "Q6") (pin "3") (pinfunction "D_3") (pintype "passive"))
      (node (ref "R19") (pin "2") (pinfunction "2_2") (pintype "passive"))
      (node (ref "U1") (pin "17") (pinfunction "SHC_17") (pintype "passive"))
    )
    (net (code "27") (name "/DRV_VCP") (class "Default")
      (node (ref "C1") (pin "1") (pinfunction "1_1") (pintype "passive"))
      (node (ref "U1") (pin "3") (pinfunction "VCP_3") (pintype "passive"))
    )
    (net (code "28") (name "/GPIO_DRVCAL_MCU_TO_DRV_3V3") (class "Default")
      (node (ref "J3") (pin "7") (pinfunction "7_7") (pintype "passive"))
      (node (ref "U1") (pin "31") (pinfunction "CAL_31") (pintype "passive"))
    )
    (net (code "29") (name "/GPIO_DRVENABLE_MCU_TO_DRV_3V3") (class "Default")
      (node (ref "J3") (pin "8") (pinfunction "8_8") (pintype "passive"))
      (node (ref "U1") (pin "30") (pinfunction "ENABLE_30") (pintype "passive"))
    )
    (net (code "30") (name "/GPIO_DRVFAULT_DRV_TO_MCU_3V3_L") (class "Default")
      (node (ref "J3") (pin "6") (pinfunction "6_6") (pintype "passive"))
      (node (ref "R11") (pin "1") (pinfunction "1_1") (pintype "passive"))
      (node (ref "U1") (pin "25") (pinfunction "~{FAULT}_25") (pintype "passive"))
    )
    (net (code "31") (name "/GPIO_MCU_TO_DRV_INL_3V3") (class "Default")
      (node (ref "J4") (pin "6") (pinfunction "6_6") (pintype "passive"))
      (node (ref "R16") (pin "1") (pinfunction "1_1") (pintype "passive"))
      (node (ref "R17") (pin "1") (pinfunction "1_1") (pintype "passive"))
      (node (ref "R18") (pin "1") (pinfunction "1_1") (pintype "passive"))
    )
    (net (code "32") (name "/ISENSE_A_DRV_TO_MCU_3V3") (class "Default")
      (node (ref "R5") (pin "1") (pinfunction "1_1") (pintype "passive"))
      (node (ref "U1") (pin "23") (pinfunction "SOA_23") (pintype "passive"))
    )
    (net (code "33") (name "/ISENSE_A_DRV_TO_MCU_FILT_3V3") (class "Default")
      (node (ref "C10") (pin "2") (pinfunction "2_2") (pintype "passive"))
      (node (ref "J5") (pin "1") (pinfunction "1_1") (pintype "passive"))
      (node (ref "R5") (pin "2") (pinfunction "2_2") (pintype "passive"))
    )
    (net (code "34") (name "/ISENSE_B_DRV_TO_MCU_3V3") (class "Default")
      (node (ref "R14") (pin "1") (pinfunction "1_1") (pintype "passive"))
      (node (ref "U1") (pin "22") (pinfunction "SOB_22") (pintype "passive"))
    )
    (net (code "35") (name "/ISENSE_B_DRV_TO_MCU_FILT_3V3") (class "Default")
      (node (ref "C14") (pin "2") (pinfunction "2_2") (pintype "passive"))
      (node (ref "J5") (pin "2") (pinfunction "2_2") (pintype "passive"))
      (node (ref "R14") (pin "2") (pinfunction "2_2") (pintype "passive"))
    )
    (net (code "36") (name "/ISENSE_C_DRV_TO_MCU_3V3") (class "Default")
      (node (ref "R24") (pin "1") (pinfunction "1_1") (pintype "passive"))
      (node (ref "U1") (pin "21") (pinfunction "SOC_21") (pintype "passive"))
    )
    (net (code "37") (name "/ISENSE_C_DRV_TO_MCU_FILT_3V3") (class "Default")
      (node (ref "C23") (pin "2") (pinfunction "2_2") (pintype "passive"))
      (node (ref "J5") (pin "3") (pinfunction "3_3") (pintype "passive"))
      (node (ref "R24") (pin "2") (pinfunction "2_2") (pintype "passive"))
    )
    (net (code "38") (name "/PWM_MCU_TO_DRV_INHA_3V3") (class "Default")
      (node (ref "J4") (pin "1") (pinfunction "1_1") (pintype "passive"))
      (node (ref "U1") (pin "34") (pinfunction "INHA_34") (pintype "passive"))
    )
    (net (code "39") (name "/PWM_MCU_TO_DRV_INHB_3V3") (class "Default")
      (node (ref "J4") (pin "3") (pinfunction "3_3") (pintype "passive"))
      (node (ref "U1") (pin "36") (pinfunction "INHB_36") (pintype "passive"))
    )
    (net (code "40") (name "/PWM_MCU_TO_DRV_INHC_3V3") (class "Default")
      (node (ref "J4") (pin "8") (pinfunction "8_8") (pintype "passive"))
      (node (ref "U1") (pin "38") (pinfunction "INHC_38") (pintype "passive"))
    )
    (net (code "41") (name "/PWM_MCU_TO_DRV_INLA_3V3") (class "Default")
      (node (ref "J4") (pin "2") (pinfunction "2_2") (pintype "passive"))
      (node (ref "R16") (pin "2") (pinfunction "2_2") (pintype "passive"))
      (node (ref "U1") (pin "35") (pinfunction "INLA_35") (pintype "passive"))
    )
    (net (code "42") (name "/PWM_MCU_TO_DRV_INLB_3V3") (class "Default")
      (node (ref "J4") (pin "4") (pinfunction "4_4") (pintype "passive"))
      (node (ref "R17") (pin "2") (pinfunction "2_2") (pintype "passive"))
      (node (ref "U1") (pin "37") (pinfunction "INLB_37") (pintype "passive"))
    )
    (net (code "43") (name "/PWM_MCU_TO_DRV_INLC_3V3") (class "Default")
      (node (ref "J4") (pin "7") (pinfunction "7_7") (pintype "passive"))
      (node (ref "R18") (pin "2") (pinfunction "2_2") (pintype "passive"))
      (node (ref "U1") (pin "39") (pinfunction "INLC_39") (pintype "passive"))
    )
    (net (code "44") (name "/SPI_CS_MCU_TO_DRV_3V3_L") (class "Default")
      (node (ref "J3") (pin "4") (pinfunction "4_4") (pintype "passive"))
      (node (ref "R8") (pin "1") (pinfunction "1_1") (pintype "passive"))
      (node (ref "U1") (pin "29") (pinfunction "~{SCS}_29") (pintype "passive"))
    )
    (net (code "45") (name "/SPI_MISO_DRV_TO_MCU_3V3") (class "Default")
      (node (ref "J3") (pin "2") (pinfunction "2_2") (pintype "passive"))
      (node (ref "R7") (pin "1") (pinfunction "1_1") (pintype "passive"))
      (node (ref "U1") (pin "26") (pinfunction "SDO_26") (pintype "passive"))
    )
    (net (code "46") (name "/SPI_MOSI_MCU_TO_DRV_3V3") (class "Default")
      (node (ref "J3") (pin "1") (pinfunction "1_1") (pintype "passive"))
      (node (ref "U1") (pin "27") (pinfunction "SDI_27") (pintype "passive"))
    )
    (net (code "47") (name "/SPI_SCLK_MCU_TO_DRV_3V3") (class "Default")
      (node (ref "J3") (pin "3") (pinfunction "3_3") (pintype "passive"))
      (node (ref "U1") (pin "28") (pinfunction "SCLK_28") (pintype "passive"))
    )
    (net (code "48") (name "/TSENSE_AB_DRV_TO_MCU_3V3") (class "Default")
      (node (ref "R22") (pin "1") (pinfunction "1_1") (pintype "passive"))
      (node (ref "U3") (pin "2") (pinfunction "VOUT_2") (pintype "passive"))
    )
    (net (code "49") (name "/TSENSE_AB_DRV_TO_MCU_FILT_3V3") (class "Default")
      (node (ref "C22") (pin "2") (pinfunction "2_2") (pintype "passive"))
      (node (ref "J6") (pin "1") (pinfunction "1_1") (pintype "passive"))
      (node (ref "R22") (pin "2") (pinfunction "2_2") (pintype "passive"))
    )
    (net (code "50") (name "/TSENSE_BC_DRV_TO_MCU_3V3") (class "Default")
      (node (ref "R26") (pin "1") (pinfunction "1_1") (pintype "passive"))
      (node (ref "U4") (pin "2") (pinfunction "VOUT_2") (pintype "passive"))
    )
    (net (code "51") (name "/TSENSE_BC_DRV_TO_MCU_FILT_3V3") (class "Default")
      (node (ref "C25") (pin "2") (pinfunction "2_2") (pintype "passive"))
      (node (ref "J6") (pin "2") (pinfunction "2_2") (pintype "passive"))
      (node (ref "R26") (pin "2") (pinfunction "2_2") (pintype "passive"))
    )
    (net (code "52") (name "/VSENSE_A_DRV_TO_MCU_3V3") (class "Default")
      (node (ref "C7") (pin "2") (pinfunction "2_2") (pintype "passive"))
      (node (ref "J5") (pin "8") (pinfunction "8_8") (pintype "passive"))
      (node (ref "R1") (pin "1") (pinfunction "1_1") (pintype "passive"))
      (node (ref "R3") (pin "2") (pinfunction "2_2") (pintype "passive"))
    )
    (net (code "53") (name "/VSENSE_B_DRV_TO_MCU_3V3") (class "Default")
      (node (ref "C13") (pin "2") (pinfunction "2_2") (pintype "passive"))
      (node (ref "J5") (pin "7") (pinfunction "7_7") (pintype "passive"))
      (node (ref "R12") (pin "2") (pinfunction "2_2") (pintype "passive"))
      (node (ref "R9") (pin "1") (pinfunction "1_1") (pintype "passive"))
    )
    (net (code "54") (name "/VSENSE_C_DRV_TO_MCU_3V3") (class "Default")
      (node (ref "C17") (pin "2") (pinfunction "2_2") (pintype "passive"))
      (node (ref "J5") (pin "6") (pinfunction "6_6") (pintype "passive"))
      (node (ref "R19") (pin "1") (pinfunction "1_1") (pintype "passive"))
      (node (ref "R21") (pin "2") (pinfunction "2_2") (pintype "passive"))
    )
    (net (code "55") (name "3V3") (class "Default")
      (node (ref "C20") (pin "2") (pinfunction "2_2") (pintype "passive"))
      (node (ref "C21") (pin "2") (pinfunction "2_2") (pintype "passive"))
      (node (ref "C24") (pin "2") (pinfunction "2_2") (pintype "passive"))
      (node (ref "J6") (pin "5") (pinfunction "5_5") (pintype "passive"))
      (node (ref "J6") (pin "6") (pinfunction "6_6") (pintype "passive"))
      (node (ref "J6") (pin "7") (pinfunction "7_7") (pintype "passive"))
      (node (ref "J6") (pin "8") (pinfunction "8_8") (pintype "passive"))
      (node (ref "R11") (pin "2") (pinfunction "2_2") (pintype "passive"))
      (node (ref "R7") (pin "2") (pinfunction "2_2") (pintype "passive"))
      (node (ref "R8") (pin "2") (pinfunction "2_2") (pintype "passive"))
      (node (ref "U2") (pin "1") (pinfunction "OUT_1") (pintype "passive"))
      (node (ref "U3") (pin "1") (pinfunction "VDD_1") (pintype "passive"))
      (node (ref "U4") (pin "1") (pinfunction "VDD_1") (pintype "passive"))
    )
    (net (code "56") (name "DRV_3V3") (class "Default")
      (node (ref "C2") (pin "2") (pinfunction "2_2") (pintype "passive"))
      (node (ref "C9") (pin "2") (pinfunction "2_2") (pintype "passive"))
      (node (ref "U1") (pin "24") (pinfunction "VREF_24") (pintype "passive"))
      (node (ref "U1") (pin "33") (pinfunction "DVDD_33") (pintype "passive"))
    )
    (net (code "57") (name "GND") (class "Default")
      (node (ref "C10") (pin "1") (pinfunction "1_1") (pintype "passive"))
      (node (ref "C11") (pin "1") (pinfunction "1_1") (pintype "passive"))
      (node (ref "C12") (pin "1") (pinfunction "1_1") (pintype "passive"))
      (node (ref "C13") (pin "1") (pinfunction "1_1") (pintype "passive"))
      (node (ref "C14") (pin "1") (pinfunction "1_1") (pintype "passive"))
      (node (ref "C15") (pin "1") (pinfunction "1_1") (pintype "passive"))
      (node (ref "C16") (pin "1") (pinfunction "1_1") (pintype "passive"))
      (node (ref "C17") (pin "1") (pinfunction "1_1") (pintype "passive"))
      (node (ref "C18") (pin "1") (pinfunction "1_1") (pintype "passive"))
      (node (ref "C19") (pin "1") (pinfunction "1_1") (pintype "passive"))
      (node (ref "C2") (pin "1") (pinfunction "1_1") (pintype "passive"))
      (node (ref "C20") (pin "1") (pinfunction "1_1") (pintype "passive"))
      (node (ref "C21") (pin "1") (pinfunction "1_1") (pintype "passive"))
      (node (ref "C22") (pin "1") (pinfunction "1_1") (pintype "passive"))
      (node (ref "C23") (pin "1") (pinfunction "1_1") (pintype "passive"))
      (node (ref "C24") (pin "1") (pinfunction "1_1") (pintype "passive"))
      (node (ref "C25") (pin "1") (pinfunction "1_1") (pintype "passive"))
      (node (ref "C26") (pin "1") (pinfunction "1_1") (pintype "passive"))
      (node (ref "C27") (pin "1") (pinfunction "1_1") (pintype "passive"))
      (node (ref "C28") (pin "2") (pinfunction "2_2") (pintype "passive"))
      (node (ref "C3") (pin "2") (pinfunction "2_2") (pintype "passive"))
      (node (ref "C4") (pin "1") (pinfunction "1_1") (pintype "passive"))
      (node (ref "C5") (pin "1") (pinfunction "1_1") (pintype "passive"))
      (node (ref "C6") (pin "1") (pinfunction "1_1") (pintype "passive"))
      (node (ref "C7") (pin "1") (pinfunction "1_1") (pintype "passive"))
      (node (ref "C9") (pin "1") (pinfunction "1_1") (pintype "passive"))
      (node (ref "J1") (pin "2") (pinfunction "2_2") (pintype "passive"))
      (node (ref "J3") (pin "5") (pinfunction "5_5") (pintype "passive"))
      (node (ref "J4") (pin "5") (pinfunction "5_5") (pintype "passive"))
      (node (ref "J5") (pin "4") (pinfunction "4_4") (pintype "passive"))
      (node (ref "J5") (pin "5") (pinfunction "5_5") (pintype "passive"))
      (node (ref "J6") (pin "3") (pinfunction "3_3") (pintype "passive"))
      (node (ref "J6") (pin "4") (pinfunction "4_4") (pintype "passive"))
      (node (ref "NT2") (pin "2") (pinfunction "2_2") (pintype "passive"))
      (node (ref "NT4") (pin "2") (pinfunction "2_2") (pintype "passive"))
      (node (ref "NT6") (pin "2") (pinfunction "2_2") (pintype "passive"))
      (node (ref "R12") (pin "1") (pinfunction "1_1") (pintype "passive"))
      (node (ref "R15") (pin "1") (pinfunction "1_1") (pintype "passive"))
      (node (ref "R21") (pin "1") (pinfunction "1_1") (pintype "passive"))
      (node (ref "R25") (pin "1") (pinfunction "1_1") (pintype "passive"))
      (node (ref "R3") (pin "1") (pinfunction "1_1") (pintype "passive"))
      (node (ref "R6") (pin "1") (pinfunction "1_1") (pintype "passive"))
      (node (ref "U1") (pin "32") (pinfunction "AGND_32") (pintype "passive"))
      (node (ref "U1") (pin "40") (pinfunction "PGND_40") (pintype "passive"))
      (node (ref "U1") (pin "41") (pinfunction "EPAD_41") (pintype "passive"))
      (node (ref "U2") (pin "3") (pinfunction "GND_3") (pintype "passive"))
      (node (ref "U3") (pin "3") (pinfunction "GND_3") (pintype "passive"))
      (node (ref "U4") (pin "3") (pinfunction "GND_3") (pintype "passive"))
    )
    (net (code "58") (name "VBUS") (class "Default")
      (node (ref "C1") (pin "2") (pinfunction "2_2") (pintype "passive"))
      (node (ref "C11") (pin "2") (pinfunction "2_2") (pintype "passive"))
      (node (ref "C12") (pin "2") (pinfunction "2_2") (pintype "passive"))
      (node (ref "C15") (pin "2") (pinfunction "2_2") (pintype "passive"))
      (node (ref "C16") (pin "2") (pinfunction "2_2") (pintype "passive"))
      (node (ref "C18") (pin "2") (pinfunction "2_2") (pintype "passive"))
      (node (ref "C19") (pin "2") (pinfunction "2_2") (pintype "passive"))
      (node (ref "C26") (pin "2") (pinfunction "2_2") (pintype "passive"))
      (node (ref "C27") (pin "2") (pinfunction "2_2") (pintype "passive"))
      (node (ref "C28") (pin "1") (pinfunction "1_1") (pintype "passive"))
      (node (ref "C3") (pin "1") (pinfunction "1_1") (pintype "passive"))
      (node (ref "C4") (pin "2") (pinfunction "2_2") (pintype "passive"))
      (node (ref "C5") (pin "2") (pinfunction "2_2") (pintype "passive"))
      (node (ref "C6") (pin "2") (pinfunction "2_2") (pintype "passive"))
      (node (ref "J1") (pin "1") (pinfunction "1_1") (pintype "passive"))
      (node (ref "Q1") (pin "3") (pinfunction "D_3") (pintype "passive"))
      (node (ref "Q3") (pin "3") (pinfunction "D_3") (pintype "passive"))
      (node (ref "Q5") (pin "3") (pinfunction "D_3") (pintype "passive"))
      (node (ref "U1") (pin "4") (pinfunction "VM_4") (pintype "passive"))
      (node (ref "U1") (pin "5") (pinfunction "VDRAIN_5") (pintype "passive"))
      (node (ref "U2") (pin "2") (pinfunction "IN_2") (pintype "passive"))
    )
    (net (code "59") (name "unconnected-(MH1-Pad1)") (class "Default")
      (node (ref "MH1") (pin "1") (pinfunction "1_1") (pintype "passive+no_connect"))
    )
    (net (code "60") (name "unconnected-(MH2-Pad1)") (class "Default")
      (node (ref "MH2") (pin "1") (pinfunction "1_1") (pintype "passive+no_connect"))
    )
    (net (code "61") (name "unconnected-(MH3-Pad1)") (class "Default")
      (node (ref "MH3") (pin "1") (pinfunction "1_1") (pintype "passive+no_connect"))
    )
    (net (code "62") (name "unconnected-(MH4-Pad1)") (class "Default")
      (node (ref "MH4") (pin "1") (pinfunction "1_1") (pintype "passive+no_connect"))
    )
  )
)
